# dashboard.net
KiCad netlist of a schematic drawn in EAGLE
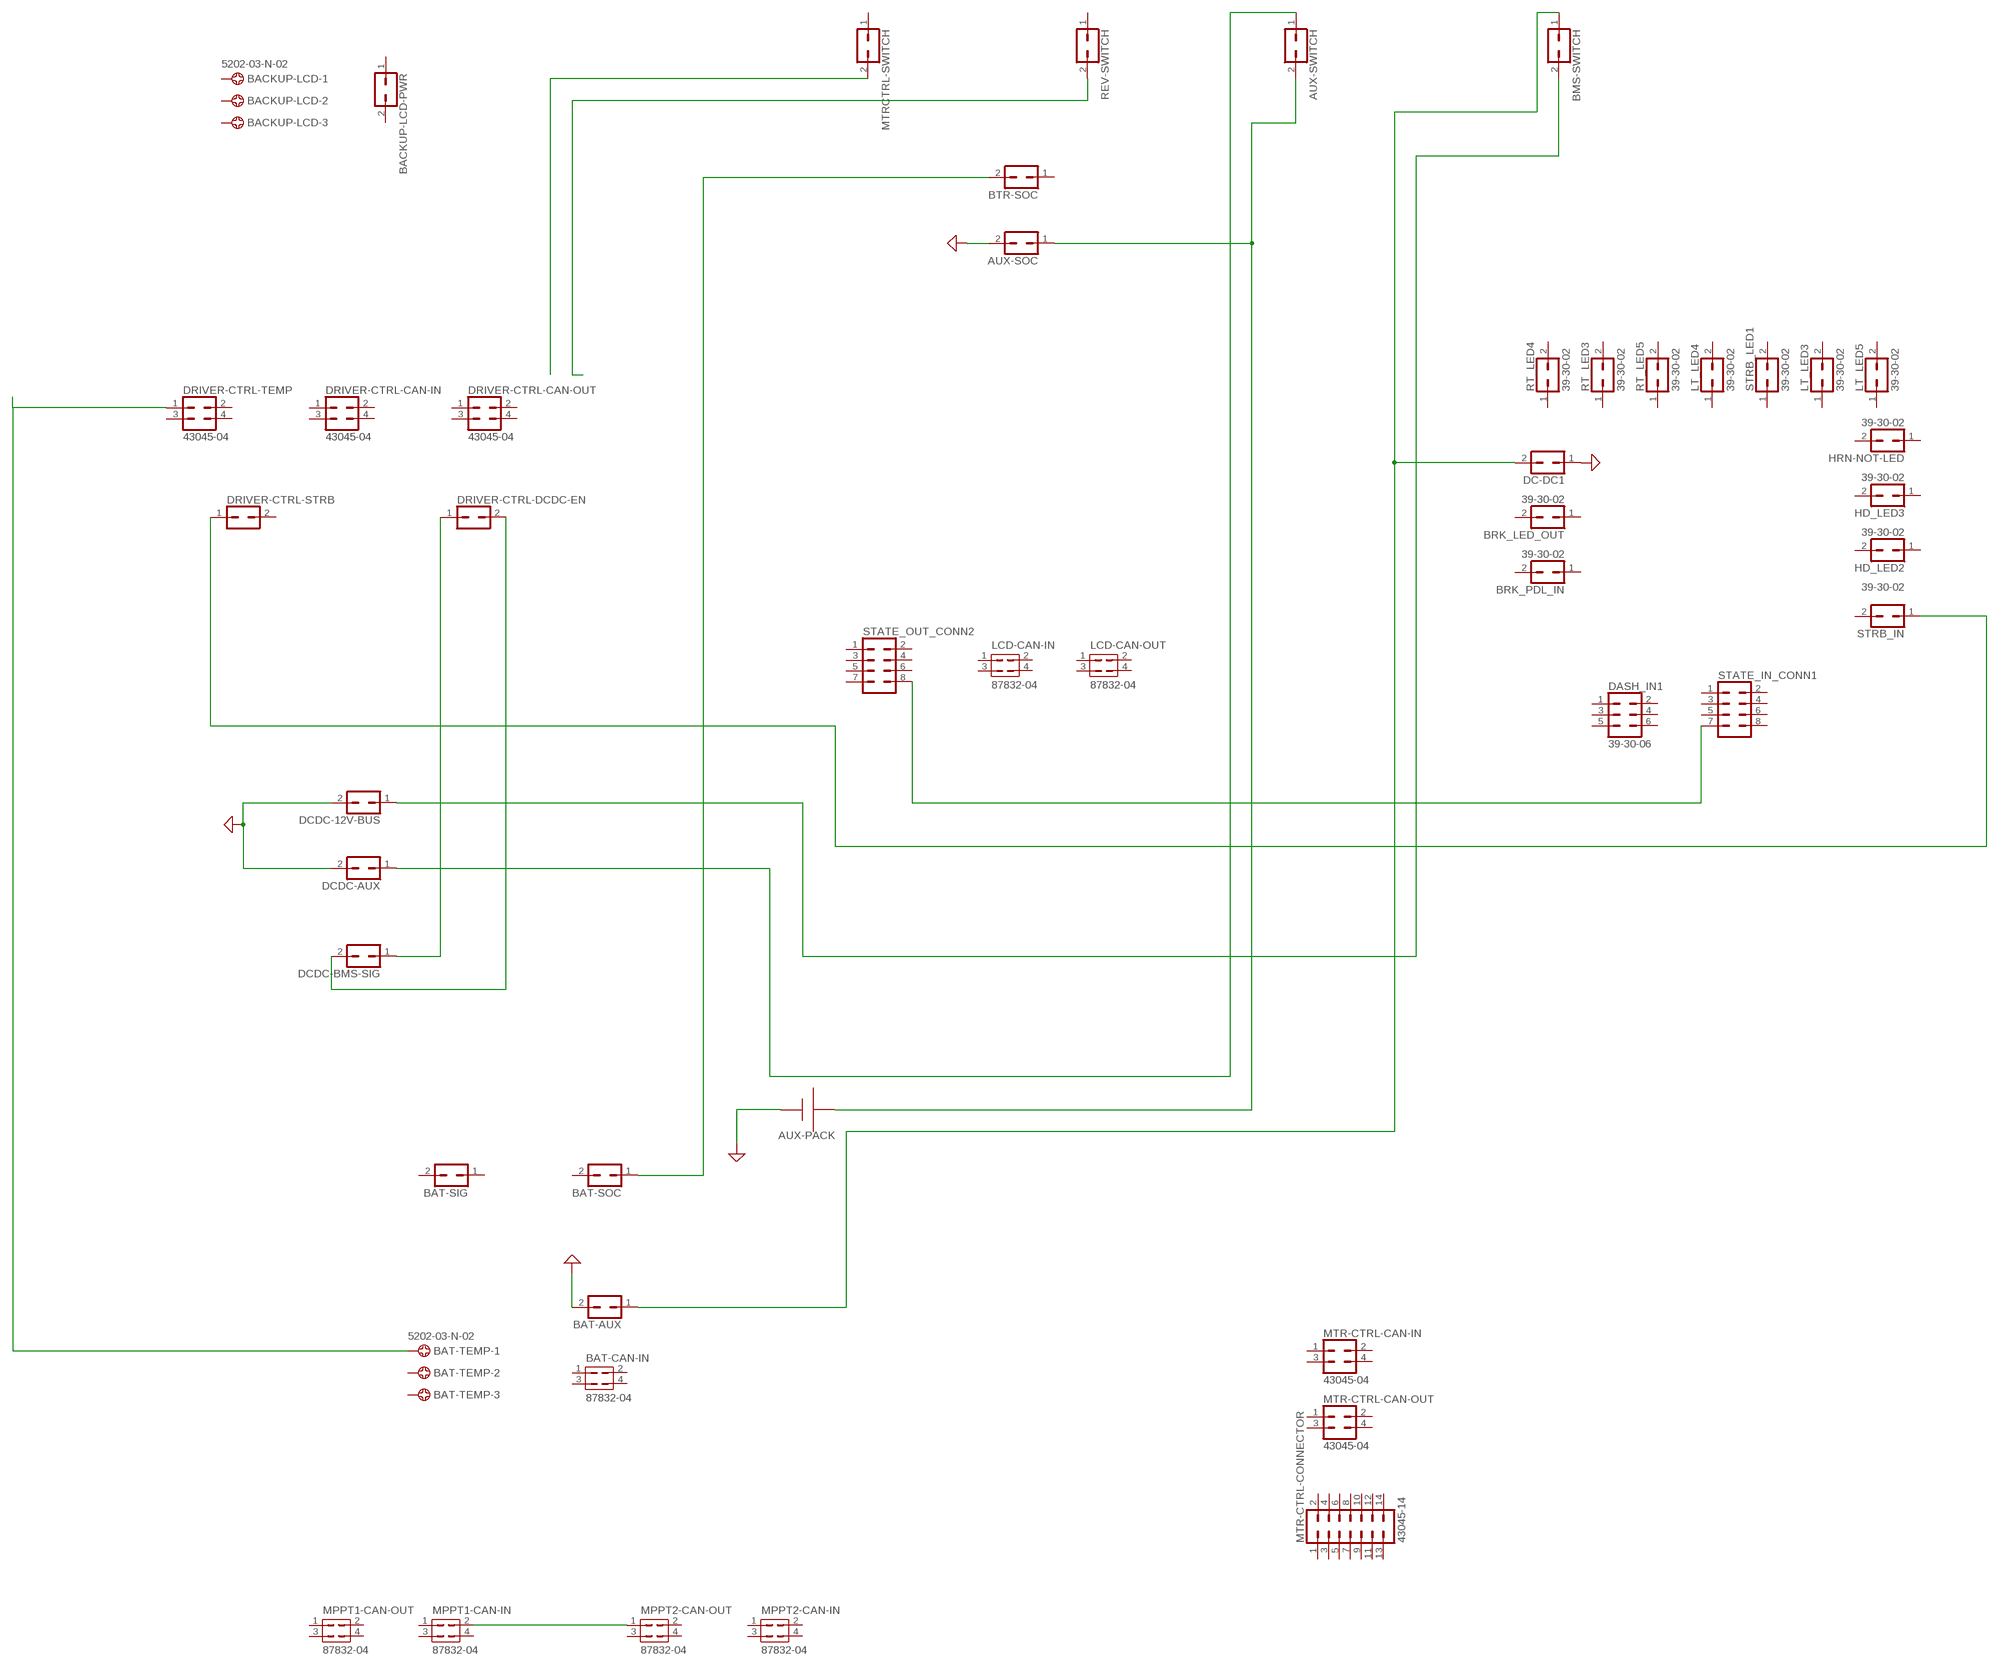
[diagram p0: schematic, sheet 1]

(export (version "E")
  (design (tool "Eeschema 10.0.6"))
  (components
    (comp (ref "AUX-PACK")
      (value "AAA")
      (footprint "eagle-import:12BH412")
      (libsource (lib "eagle-import") (part "AAA"))
    )
    (comp (ref "AUX-SOC")
      (value "39-30-02")
      (footprint "eagle-import:39-30-_02_")
      (libsource (lib "eagle-import") (part "39-30-?02?"))
    )
    (comp (ref "AUX-SWITCH")
      (value "39-30-02")
      (footprint "eagle-import:39-30-_02_")
      (libsource (lib "eagle-import") (part "39-30-?02?"))
    )
    (comp (ref "BACKUP-LCD")
      (value "5202-03-N-02")
      (footprint "eagle-import:5202-03-N-02")
      (libsource (lib "eagle-import") (part "5202-03-N-02"))
    )
    (comp (ref "BACKUP-LCD-PWR")
      (value "39-30-02")
      (footprint "eagle-import:39-30-_02_")
      (libsource (lib "eagle-import") (part "39-30-?02?"))
    )
    (comp (ref "BAT-AUX")
      (value "39-30-02")
      (footprint "eagle-import:39-30-_02_")
      (libsource (lib "eagle-import") (part "39-30-?02?"))
    )
    (comp (ref "BAT-CAN-IN")
      (value "87832-04")
      (footprint "eagle-import:87832-04")
      (fields (field (name "MF") "MOLEX"))
      (libsource (lib "eagle-import") (part "87832-04"))
    )
    (comp (ref "BAT-SIG")
      (value "39-30-02")
      (footprint "eagle-import:39-30-_02_")
      (libsource (lib "eagle-import") (part "39-30-?02?"))
    )
    (comp (ref "BAT-SOC")
      (value "39-30-02")
      (footprint "eagle-import:39-30-_02_")
      (libsource (lib "eagle-import") (part "39-30-?02?"))
    )
    (comp (ref "BAT-TEMP")
      (value "5202-03-N-02")
      (footprint "eagle-import:5202-03-N-02")
      (libsource (lib "eagle-import") (part "5202-03-N-02"))
    )
    (comp (ref "BMS-SWITCH")
      (value "39-30-02")
      (footprint "eagle-import:39-30-_02_")
      (libsource (lib "eagle-import") (part "39-30-?02?"))
    )
    (comp (ref "BRK_LED_OUT")
      (value "39-30-02")
      (footprint "eagle-import:39-30-_02_")
      (libsource (lib "eagle-import") (part "39-30-?02?"))
    )
    (comp (ref "BRK_PDL_IN")
      (value "39-30-02")
      (footprint "eagle-import:39-30-_02_")
      (libsource (lib "eagle-import") (part "39-30-?02?"))
    )
    (comp (ref "BTR-SOC")
      (value "39-30-02")
      (footprint "eagle-import:39-30-_02_")
      (libsource (lib "eagle-import") (part "39-30-?02?"))
    )
    (comp (ref "DASH_IN1")
      (value "39-30-06")
      (footprint "eagle-import:39-30-_06_")
      (libsource (lib "eagle-import") (part "39-30-?06?"))
    )
    (comp (ref "DC-DC1")
      (value "39-30-02")
      (footprint "eagle-import:39-30-_02_")
      (libsource (lib "eagle-import") (part "39-30-?02?"))
    )
    (comp (ref "DCDC-12V-BUS")
      (value "39-30-02")
      (footprint "eagle-import:39-30-_02_")
      (libsource (lib "eagle-import") (part "39-30-?02?"))
    )
    (comp (ref "DCDC-AUX")
      (value "39-30-02")
      (footprint "eagle-import:39-30-_02_")
      (libsource (lib "eagle-import") (part "39-30-?02?"))
    )
    (comp (ref "DCDC-BMS-SIG")
      (value "39-30-02")
      (footprint "eagle-import:39-30-_02_")
      (libsource (lib "eagle-import") (part "39-30-?02?"))
    )
    (comp (ref "DRIVER-CTRL-CAN-IN")
      (value "43045-04")
      (footprint "eagle-import:43045-04")
      (libsource (lib "eagle-import") (part "43045-04"))
    )
    (comp (ref "DRIVER-CTRL-CAN-OUT")
      (value "43045-04")
      (footprint "eagle-import:43045-04")
      (libsource (lib "eagle-import") (part "43045-04"))
    )
    (comp (ref "DRIVER-CTRL-DCDC-EN")
      (value "43045-02")
      (footprint "eagle-import:43045-02")
      (libsource (lib "eagle-import") (part "43045-02"))
    )
    (comp (ref "DRIVER-CTRL-STRB")
      (value "43045-02")
      (footprint "eagle-import:43045-02")
      (libsource (lib "eagle-import") (part "43045-02"))
    )
    (comp (ref "DRIVER-CTRL-TEMP")
      (value "43045-04")
      (footprint "eagle-import:43045-04")
      (libsource (lib "eagle-import") (part "43045-04"))
    )
    (comp (ref "HD_LED2")
      (value "39-30-02")
      (footprint "eagle-import:39-30-_02_")
      (libsource (lib "eagle-import") (part "39-30-?02?"))
    )
    (comp (ref "HD_LED3")
      (value "39-30-02")
      (footprint "eagle-import:39-30-_02_")
      (libsource (lib "eagle-import") (part "39-30-?02?"))
    )
    (comp (ref "HRN-NOT-LED")
      (value "39-30-02")
      (footprint "eagle-import:39-30-_02_")
      (libsource (lib "eagle-import") (part "39-30-?02?"))
    )
    (comp (ref "LCD-CAN-IN")
      (value "87832-04")
      (footprint "eagle-import:87832-04")
      (fields (field (name "MF") "MOLEX"))
      (libsource (lib "eagle-import") (part "87832-04"))
    )
    (comp (ref "LCD-CAN-OUT")
      (value "87832-04")
      (footprint "eagle-import:87832-04")
      (fields (field (name "MF") "MOLEX"))
      (libsource (lib "eagle-import") (part "87832-04"))
    )
    (comp (ref "LT_LED3")
      (value "39-30-02")
      (footprint "eagle-import:39-30-_02_")
      (libsource (lib "eagle-import") (part "39-30-?02?"))
    )
    (comp (ref "LT_LED4")
      (value "39-30-02")
      (footprint "eagle-import:39-30-_02_")
      (libsource (lib "eagle-import") (part "39-30-?02?"))
    )
    (comp (ref "LT_LED5")
      (value "39-30-02")
      (footprint "eagle-import:39-30-_02_")
      (libsource (lib "eagle-import") (part "39-30-?02?"))
    )
    (comp (ref "MPPT1-CAN-IN")
      (value "87832-04")
      (footprint "eagle-import:87832-04")
      (fields (field (name "MF") "MOLEX"))
      (libsource (lib "eagle-import") (part "87832-04"))
    )
    (comp (ref "MPPT1-CAN-OUT")
      (value "87832-04")
      (footprint "eagle-import:87832-04")
      (fields (field (name "MF") "MOLEX"))
      (libsource (lib "eagle-import") (part "87832-04"))
    )
    (comp (ref "MPPT2-CAN-IN")
      (value "87832-04")
      (footprint "eagle-import:87832-04")
      (fields (field (name "MF") "MOLEX"))
      (libsource (lib "eagle-import") (part "87832-04"))
    )
    (comp (ref "MPPT2-CAN-OUT")
      (value "87832-04")
      (footprint "eagle-import:87832-04")
      (fields (field (name "MF") "MOLEX"))
      (libsource (lib "eagle-import") (part "87832-04"))
    )
    (comp (ref "MTR-CTRL-CAN-IN")
      (value "43045-04")
      (footprint "eagle-import:43045-04")
      (libsource (lib "eagle-import") (part "43045-04"))
    )
    (comp (ref "MTR-CTRL-CAN-OUT")
      (value "43045-04")
      (footprint "eagle-import:43045-04")
      (libsource (lib "eagle-import") (part "43045-04"))
    )
    (comp (ref "MTR-CTRL-CONNECTOR")
      (value "43045-14")
      (footprint "eagle-import:43045-14")
      (libsource (lib "eagle-import") (part "43045-14"))
    )
    (comp (ref "MTRCTRL-SWITCH")
      (value "39-30-02")
      (footprint "eagle-import:39-30-_02_")
      (libsource (lib "eagle-import") (part "39-30-?02?"))
    )
    (comp (ref "REV-SWITCH")
      (value "39-30-02")
      (footprint "eagle-import:39-30-_02_")
      (libsource (lib "eagle-import") (part "39-30-?02?"))
    )
    (comp (ref "RT_LED3")
      (value "39-30-02")
      (footprint "eagle-import:39-30-_02_")
      (libsource (lib "eagle-import") (part "39-30-?02?"))
    )
    (comp (ref "RT_LED4")
      (value "39-30-02")
      (footprint "eagle-import:39-30-_02_")
      (libsource (lib "eagle-import") (part "39-30-?02?"))
    )
    (comp (ref "RT_LED5")
      (value "39-30-02")
      (footprint "eagle-import:39-30-_02_")
      (libsource (lib "eagle-import") (part "39-30-?02?"))
    )
    (comp (ref "STATE_IN_CONN1")
      (value "39-30-08")
      (footprint "eagle-import:39-30-_08_")
      (libsource (lib "eagle-import") (part "39-30-?08?"))
    )
    (comp (ref "STATE_OUT_CONN2")
      (value "39-30-08")
      (footprint "eagle-import:39-30-_08_")
      (libsource (lib "eagle-import") (part "39-30-?08?"))
    )
    (comp (ref "STRB_IN")
      (value "39-30-02")
      (footprint "eagle-import:39-30-_02_")
      (libsource (lib "eagle-import") (part "39-30-?02?"))
    )
    (comp (ref "STRB_LED1")
      (value "39-30-02")
      (footprint "eagle-import:39-30-_02_")
      (libsource (lib "eagle-import") (part "39-30-?02?"))
    )
  )
  (nets
    (net (code "1") (name "Net-(AUX-PACK-Pad-)") (class "Default")
      (node (ref "AUX-PACK") (pin "-") (pinfunction "-_-") (pintype "bidirectional"))
      (node (ref "AUX-SOC") (pin "1") (pinfunction "1_1") (pintype "passive"))
      (node (ref "AUX-SWITCH") (pin "2") (pinfunction "2_2") (pintype "passive"))
    )
    (net (code "2") (name "Net-(AUX-SWITCH-Pad1)") (class "Default")
      (node (ref "AUX-SWITCH") (pin "1") (pinfunction "1_1") (pintype "passive"))
      (node (ref "DCDC-AUX") (pin "1") (pinfunction "1_1") (pintype "passive"))
    )
    (net (code "3") (name "Net-(BAT-AUX-Pad1)") (class "Default")
      (node (ref "BAT-AUX") (pin "1") (pinfunction "1_1") (pintype "passive"))
      (node (ref "BMS-SWITCH") (pin "1") (pinfunction "1_1") (pintype "passive"))
      (node (ref "DC-DC1") (pin "2") (pinfunction "2_2") (pintype "passive"))
    )
    (net (code "4") (name "Net-(BAT-SOC-Pad1)") (class "Default")
      (node (ref "BAT-SOC") (pin "1") (pinfunction "1_1") (pintype "passive"))
      (node (ref "BTR-SOC") (pin "2") (pinfunction "2_2") (pintype "passive"))
    )
    (net (code "5") (name "Net-(BAT-TEMP-Pad1)") (class "Default")
      (node (ref "BAT-TEMP") (pin "1") (pinfunction "1_1") (pintype "passive"))
      (node (ref "DRIVER-CTRL-TEMP") (pin "1") (pinfunction "1_1") (pintype "passive"))
    )
    (net (code "6") (name "Net-(BMS-SWITCH-Pad2)") (class "Default")
      (node (ref "BMS-SWITCH") (pin "2") (pinfunction "2_2") (pintype "passive"))
      (node (ref "DCDC-12V-BUS") (pin "1") (pinfunction "1_1") (pintype "passive"))
    )
    (net (code "7") (name "Net-(DCDC-BMS-SIG-Pad1)") (class "Default")
      (node (ref "DCDC-BMS-SIG") (pin "1") (pinfunction "1_1") (pintype "passive"))
      (node (ref "DRIVER-CTRL-DCDC-EN") (pin "1") (pinfunction "1_1") (pintype "passive"))
    )
    (net (code "8") (name "Net-(DCDC-BMS-SIG-Pad2)") (class "Default")
      (node (ref "DCDC-BMS-SIG") (pin "2") (pinfunction "2_2") (pintype "passive"))
      (node (ref "DRIVER-CTRL-DCDC-EN") (pin "2") (pinfunction "2_2") (pintype "passive"))
    )
    (net (code "9") (name "Net-(DRIVER-CTRL-STRB-Pad1)") (class "Default")
      (node (ref "DRIVER-CTRL-STRB") (pin "1") (pinfunction "1_1") (pintype "passive"))
      (node (ref "STRB_IN") (pin "1") (pinfunction "1_1") (pintype "passive"))
    )
    (net (code "10") (name "Net-(MPPT1-CAN-IN-Pad2)") (class "Default")
      (node (ref "MPPT1-CAN-IN") (pin "2") (pinfunction "2_2") (pintype "passive"))
      (node (ref "MPPT2-CAN-OUT") (pin "1") (pinfunction "1_1") (pintype "passive"))
    )
    (net (code "11") (name "Net-(STATE_IN_CONN1-Pad7)") (class "Default")
      (node (ref "STATE_IN_CONN1") (pin "7") (pinfunction "7_7") (pintype "passive"))
      (node (ref "STATE_OUT_CONN2") (pin "8") (pinfunction "8_8") (pintype "passive"))
    )
    (net (code "12") (name "SUP") (class "Default")
      (node (ref "AUX-PACK") (pin "+") (pinfunction "+_+") (pintype "bidirectional"))
      (node (ref "AUX-SOC") (pin "2") (pinfunction "2_2") (pintype "passive"))
      (node (ref "BAT-AUX") (pin "2") (pinfunction "2_2") (pintype "passive"))
      (node (ref "DC-DC1") (pin "1") (pinfunction "1_1") (pintype "passive"))
      (node (ref "DCDC-12V-BUS") (pin "2") (pinfunction "2_2") (pintype "passive"))
      (node (ref "DCDC-AUX") (pin "2") (pinfunction "2_2") (pintype "passive"))
    )
    (net (code "13") (name "unconnected-(BACKUP-LCD-PWR-Pad1)") (class "Default")
      (node (ref "BACKUP-LCD-PWR") (pin "1") (pinfunction "1_1") (pintype "passive"))
    )
    (net (code "14") (name "unconnected-(BACKUP-LCD-PWR-Pad2)") (class "Default")
      (node (ref "BACKUP-LCD-PWR") (pin "2") (pinfunction "2_2") (pintype "passive"))
    )
    (net (code "15") (name "unconnected-(BACKUP-LCD-Pad1)") (class "Default")
      (node (ref "BACKUP-LCD") (pin "1") (pinfunction "1_1") (pintype "passive"))
    )
    (net (code "16") (name "unconnected-(BACKUP-LCDB-1-Pad2)") (class "Default")
      (node (ref "BACKUP-LCD") (pin "2") (pinfunction "1_2") (pintype "passive"))
    )
    (net (code "17") (name "unconnected-(BACKUP-LCDC-1-Pad3)") (class "Default")
      (node (ref "BACKUP-LCD") (pin "3") (pinfunction "1_3") (pintype "passive"))
    )
    (net (code "18") (name "unconnected-(BAT-CAN-IN-Pad1)") (class "Default")
      (node (ref "BAT-CAN-IN") (pin "1") (pinfunction "1_1") (pintype "passive"))
    )
    (net (code "19") (name "unconnected-(BAT-CAN-IN-Pad2)") (class "Default")
      (node (ref "BAT-CAN-IN") (pin "2") (pinfunction "2_2") (pintype "passive"))
    )
    (net (code "20") (name "unconnected-(BAT-CAN-IN-Pad3)") (class "Default")
      (node (ref "BAT-CAN-IN") (pin "3") (pinfunction "3_3") (pintype "passive"))
    )
    (net (code "21") (name "unconnected-(BAT-CAN-IN-Pad4)") (class "Default")
      (node (ref "BAT-CAN-IN") (pin "4") (pinfunction "4_4") (pintype "passive"))
    )
    (net (code "22") (name "unconnected-(BAT-SIG-Pad1)") (class "Default")
      (node (ref "BAT-SIG") (pin "1") (pinfunction "1_1") (pintype "passive"))
    )
    (net (code "23") (name "unconnected-(BAT-SIG-Pad2)") (class "Default")
      (node (ref "BAT-SIG") (pin "2") (pinfunction "2_2") (pintype "passive"))
    )
    (net (code "24") (name "unconnected-(BAT-SOC-Pad2)") (class "Default")
      (node (ref "BAT-SOC") (pin "2") (pinfunction "2_2") (pintype "passive"))
    )
    (net (code "25") (name "unconnected-(BAT-TEMPB-1-Pad2)") (class "Default")
      (node (ref "BAT-TEMP") (pin "2") (pinfunction "1_2") (pintype "passive"))
    )
    (net (code "26") (name "unconnected-(BAT-TEMPC-1-Pad3)") (class "Default")
      (node (ref "BAT-TEMP") (pin "3") (pinfunction "1_3") (pintype "passive"))
    )
    (net (code "27") (name "unconnected-(BRK_LED_OUT-Pad1)") (class "Default")
      (node (ref "BRK_LED_OUT") (pin "1") (pinfunction "1_1") (pintype "passive"))
    )
    (net (code "28") (name "unconnected-(BRK_LED_OUT-Pad2)") (class "Default")
      (node (ref "BRK_LED_OUT") (pin "2") (pinfunction "2_2") (pintype "passive"))
    )
    (net (code "29") (name "unconnected-(BRK_PDL_IN-Pad1)") (class "Default")
      (node (ref "BRK_PDL_IN") (pin "1") (pinfunction "1_1") (pintype "passive"))
    )
    (net (code "30") (name "unconnected-(BRK_PDL_IN-Pad2)") (class "Default")
      (node (ref "BRK_PDL_IN") (pin "2") (pinfunction "2_2") (pintype "passive"))
    )
    (net (code "31") (name "unconnected-(BTR-SOC-Pad1)") (class "Default")
      (node (ref "BTR-SOC") (pin "1") (pinfunction "1_1") (pintype "passive"))
    )
    (net (code "32") (name "unconnected-(DASH_IN1-Pad1)") (class "Default")
      (node (ref "DASH_IN1") (pin "1") (pinfunction "1_1") (pintype "passive"))
    )
    (net (code "33") (name "unconnected-(DASH_IN1-Pad2)") (class "Default")
      (node (ref "DASH_IN1") (pin "2") (pinfunction "2_2") (pintype "passive"))
    )
    (net (code "34") (name "unconnected-(DASH_IN1-Pad3)") (class "Default")
      (node (ref "DASH_IN1") (pin "3") (pinfunction "3_3") (pintype "passive"))
    )
    (net (code "35") (name "unconnected-(DASH_IN1-Pad4)") (class "Default")
      (node (ref "DASH_IN1") (pin "4") (pinfunction "4_4") (pintype "passive"))
    )
    (net (code "36") (name "unconnected-(DASH_IN1-Pad5)") (class "Default")
      (node (ref "DASH_IN1") (pin "5") (pinfunction "5_5") (pintype "passive"))
    )
    (net (code "37") (name "unconnected-(DASH_IN1-Pad6)") (class "Default")
      (node (ref "DASH_IN1") (pin "6") (pinfunction "6_6") (pintype "passive"))
    )
    (net (code "38") (name "unconnected-(DRIVER-CTRL-CAN-IN-Pad1)") (class "Default")
      (node (ref "DRIVER-CTRL-CAN-IN") (pin "1") (pinfunction "1_1") (pintype "passive"))
    )
    (net (code "39") (name "unconnected-(DRIVER-CTRL-CAN-IN-Pad2)") (class "Default")
      (node (ref "DRIVER-CTRL-CAN-IN") (pin "2") (pinfunction "2_2") (pintype "passive"))
    )
    (net (code "40") (name "unconnected-(DRIVER-CTRL-CAN-IN-Pad3)") (class "Default")
      (node (ref "DRIVER-CTRL-CAN-IN") (pin "3") (pinfunction "3_3") (pintype "passive"))
    )
    (net (code "41") (name "unconnected-(DRIVER-CTRL-CAN-IN-Pad4)") (class "Default")
      (node (ref "DRIVER-CTRL-CAN-IN") (pin "4") (pinfunction "4_4") (pintype "passive"))
    )
    (net (code "42") (name "unconnected-(DRIVER-CTRL-CAN-OUT-Pad1)") (class "Default")
      (node (ref "DRIVER-CTRL-CAN-OUT") (pin "1") (pinfunction "1_1") (pintype "passive"))
    )
    (net (code "43") (name "unconnected-(DRIVER-CTRL-CAN-OUT-Pad2)") (class "Default")
      (node (ref "DRIVER-CTRL-CAN-OUT") (pin "2") (pinfunction "2_2") (pintype "passive"))
    )
    (net (code "44") (name "unconnected-(DRIVER-CTRL-CAN-OUT-Pad3)") (class "Default")
      (node (ref "DRIVER-CTRL-CAN-OUT") (pin "3") (pinfunction "3_3") (pintype "passive"))
    )
    (net (code "45") (name "unconnected-(DRIVER-CTRL-CAN-OUT-Pad4)") (class "Default")
      (node (ref "DRIVER-CTRL-CAN-OUT") (pin "4") (pinfunction "4_4") (pintype "passive"))
    )
    (net (code "46") (name "unconnected-(DRIVER-CTRL-STRB-Pad2)") (class "Default")
      (node (ref "DRIVER-CTRL-STRB") (pin "2") (pinfunction "2_2") (pintype "passive"))
    )
    (net (code "47") (name "unconnected-(DRIVER-CTRL-TEMP-Pad2)") (class "Default")
      (node (ref "DRIVER-CTRL-TEMP") (pin "2") (pinfunction "2_2") (pintype "passive"))
    )
    (net (code "48") (name "unconnected-(DRIVER-CTRL-TEMP-Pad3)") (class "Default")
      (node (ref "DRIVER-CTRL-TEMP") (pin "3") (pinfunction "3_3") (pintype "passive"))
    )
    (net (code "49") (name "unconnected-(DRIVER-CTRL-TEMP-Pad4)") (class "Default")
      (node (ref "DRIVER-CTRL-TEMP") (pin "4") (pinfunction "4_4") (pintype "passive"))
    )
    (net (code "50") (name "unconnected-(HD_LED2-Pad1)") (class "Default")
      (node (ref "HD_LED2") (pin "1") (pinfunction "1_1") (pintype "passive"))
    )
    (net (code "51") (name "unconnected-(HD_LED2-Pad2)") (class "Default")
      (node (ref "HD_LED2") (pin "2") (pinfunction "2_2") (pintype "passive"))
    )
    (net (code "52") (name "unconnected-(HD_LED3-Pad1)") (class "Default")
      (node (ref "HD_LED3") (pin "1") (pinfunction "1_1") (pintype "passive"))
    )
    (net (code "53") (name "unconnected-(HD_LED3-Pad2)") (class "Default")
      (node (ref "HD_LED3") (pin "2") (pinfunction "2_2") (pintype "passive"))
    )
    (net (code "54") (name "unconnected-(HRN-NOT-LED-Pad1)") (class "Default")
      (node (ref "HRN-NOT-LED") (pin "1") (pinfunction "1_1") (pintype "passive"))
    )
    (net (code "55") (name "unconnected-(HRN-NOT-LED-Pad2)") (class "Default")
      (node (ref "HRN-NOT-LED") (pin "2") (pinfunction "2_2") (pintype "passive"))
    )
    (net (code "56") (name "unconnected-(LCD-CAN-IN-Pad1)") (class "Default")
      (node (ref "LCD-CAN-IN") (pin "1") (pinfunction "1_1") (pintype "passive"))
    )
    (net (code "57") (name "unconnected-(LCD-CAN-IN-Pad2)") (class "Default")
      (node (ref "LCD-CAN-IN") (pin "2") (pinfunction "2_2") (pintype "passive"))
    )
    (net (code "58") (name "unconnected-(LCD-CAN-IN-Pad3)") (class "Default")
      (node (ref "LCD-CAN-IN") (pin "3") (pinfunction "3_3") (pintype "passive"))
    )
    (net (code "59") (name "unconnected-(LCD-CAN-IN-Pad4)") (class "Default")
      (node (ref "LCD-CAN-IN") (pin "4") (pinfunction "4_4") (pintype "passive"))
    )
    (net (code "60") (name "unconnected-(LCD-CAN-OUT-Pad1)") (class "Default")
      (node (ref "LCD-CAN-OUT") (pin "1") (pinfunction "1_1") (pintype "passive"))
    )
    (net (code "61") (name "unconnected-(LCD-CAN-OUT-Pad2)") (class "Default")
      (node (ref "LCD-CAN-OUT") (pin "2") (pinfunction "2_2") (pintype "passive"))
    )
    (net (code "62") (name "unconnected-(LCD-CAN-OUT-Pad3)") (class "Default")
      (node (ref "LCD-CAN-OUT") (pin "3") (pinfunction "3_3") (pintype "passive"))
    )
    (net (code "63") (name "unconnected-(LCD-CAN-OUT-Pad4)") (class "Default")
      (node (ref "LCD-CAN-OUT") (pin "4") (pinfunction "4_4") (pintype "passive"))
    )
    (net (code "64") (name "unconnected-(LT_LED3-Pad1)") (class "Default")
      (node (ref "LT_LED3") (pin "1") (pinfunction "1_1") (pintype "passive"))
    )
    (net (code "65") (name "unconnected-(LT_LED3-Pad2)") (class "Default")
      (node (ref "LT_LED3") (pin "2") (pinfunction "2_2") (pintype "passive"))
    )
    (net (code "66") (name "unconnected-(LT_LED4-Pad1)") (class "Default")
      (node (ref "LT_LED4") (pin "1") (pinfunction "1_1") (pintype "passive"))
    )
    (net (code "67") (name "unconnected-(LT_LED4-Pad2)") (class "Default")
      (node (ref "LT_LED4") (pin "2") (pinfunction "2_2") (pintype "passive"))
    )
    (net (code "68") (name "unconnected-(LT_LED5-Pad1)") (class "Default")
      (node (ref "LT_LED5") (pin "1") (pinfunction "1_1") (pintype "passive"))
    )
    (net (code "69") (name "unconnected-(LT_LED5-Pad2)") (class "Default")
      (node (ref "LT_LED5") (pin "2") (pinfunction "2_2") (pintype "passive"))
    )
    (net (code "70") (name "unconnected-(MPPT1-CAN-IN-Pad1)") (class "Default")
      (node (ref "MPPT1-CAN-IN") (pin "1") (pinfunction "1_1") (pintype "passive"))
    )
    (net (code "71") (name "unconnected-(MPPT1-CAN-IN-Pad3)") (class "Default")
      (node (ref "MPPT1-CAN-IN") (pin "3") (pinfunction "3_3") (pintype "passive"))
    )
    (net (code "72") (name "unconnected-(MPPT1-CAN-IN-Pad4)") (class "Default")
      (node (ref "MPPT1-CAN-IN") (pin "4") (pinfunction "4_4") (pintype "passive"))
    )
    (net (code "73") (name "unconnected-(MPPT1-CAN-OUT-Pad1)") (class "Default")
      (node (ref "MPPT1-CAN-OUT") (pin "1") (pinfunction "1_1") (pintype "passive"))
    )
    (net (code "74") (name "unconnected-(MPPT1-CAN-OUT-Pad2)") (class "Default")
      (node (ref "MPPT1-CAN-OUT") (pin "2") (pinfunction "2_2") (pintype "passive"))
    )
    (net (code "75") (name "unconnected-(MPPT1-CAN-OUT-Pad3)") (class "Default")
      (node (ref "MPPT1-CAN-OUT") (pin "3") (pinfunction "3_3") (pintype "passive"))
    )
    (net (code "76") (name "unconnected-(MPPT1-CAN-OUT-Pad4)") (class "Default")
      (node (ref "MPPT1-CAN-OUT") (pin "4") (pinfunction "4_4") (pintype "passive"))
    )
    (net (code "77") (name "unconnected-(MPPT2-CAN-IN-Pad1)") (class "Default")
      (node (ref "MPPT2-CAN-IN") (pin "1") (pinfunction "1_1") (pintype "passive"))
    )
    (net (code "78") (name "unconnected-(MPPT2-CAN-IN-Pad2)") (class "Default")
      (node (ref "MPPT2-CAN-IN") (pin "2") (pinfunction "2_2") (pintype "passive"))
    )
    (net (code "79") (name "unconnected-(MPPT2-CAN-IN-Pad3)") (class "Default")
      (node (ref "MPPT2-CAN-IN") (pin "3") (pinfunction "3_3") (pintype "passive"))
    )
    (net (code "80") (name "unconnected-(MPPT2-CAN-IN-Pad4)") (class "Default")
      (node (ref "MPPT2-CAN-IN") (pin "4") (pinfunction "4_4") (pintype "passive"))
    )
    (net (code "81") (name "unconnected-(MPPT2-CAN-OUT-Pad2)") (class "Default")
      (node (ref "MPPT2-CAN-OUT") (pin "2") (pinfunction "2_2") (pintype "passive"))
    )
    (net (code "82") (name "unconnected-(MPPT2-CAN-OUT-Pad3)") (class "Default")
      (node (ref "MPPT2-CAN-OUT") (pin "3") (pinfunction "3_3") (pintype "passive"))
    )
    (net (code "83") (name "unconnected-(MPPT2-CAN-OUT-Pad4)") (class "Default")
      (node (ref "MPPT2-CAN-OUT") (pin "4") (pinfunction "4_4") (pintype "passive"))
    )
    (net (code "84") (name "unconnected-(MTR-CTRL-CAN-IN-Pad1)") (class "Default")
      (node (ref "MTR-CTRL-CAN-IN") (pin "1") (pinfunction "1_1") (pintype "passive"))
    )
    (net (code "85") (name "unconnected-(MTR-CTRL-CAN-IN-Pad2)") (class "Default")
      (node (ref "MTR-CTRL-CAN-IN") (pin "2") (pinfunction "2_2") (pintype "passive"))
    )
    (net (code "86") (name "unconnected-(MTR-CTRL-CAN-IN-Pad3)") (class "Default")
      (node (ref "MTR-CTRL-CAN-IN") (pin "3") (pinfunction "3_3") (pintype "passive"))
    )
    (net (code "87") (name "unconnected-(MTR-CTRL-CAN-IN-Pad4)") (class "Default")
      (node (ref "MTR-CTRL-CAN-IN") (pin "4") (pinfunction "4_4") (pintype "passive"))
    )
    (net (code "88") (name "unconnected-(MTR-CTRL-CAN-OUT-Pad1)") (class "Default")
      (node (ref "MTR-CTRL-CAN-OUT") (pin "1") (pinfunction "1_1") (pintype "passive"))
    )
    (net (code "89") (name "unconnected-(MTR-CTRL-CAN-OUT-Pad2)") (class "Default")
      (node (ref "MTR-CTRL-CAN-OUT") (pin "2") (pinfunction "2_2") (pintype "passive"))
    )
    (net (code "90") (name "unconnected-(MTR-CTRL-CAN-OUT-Pad3)") (class "Default")
      (node (ref "MTR-CTRL-CAN-OUT") (pin "3") (pinfunction "3_3") (pintype "passive"))
    )
    (net (code "91") (name "unconnected-(MTR-CTRL-CAN-OUT-Pad4)") (class "Default")
      (node (ref "MTR-CTRL-CAN-OUT") (pin "4") (pinfunction "4_4") (pintype "passive"))
    )
    (net (code "92") (name "unconnected-(MTR-CTRL-CONNECTOR-Pad1)") (class "Default")
      (node (ref "MTR-CTRL-CONNECTOR") (pin "1") (pinfunction "1_1") (pintype "passive"))
    )
    (net (code "93") (name "unconnected-(MTR-CTRL-CONNECTOR-Pad2)") (class "Default")
      (node (ref "MTR-CTRL-CONNECTOR") (pin "2") (pinfunction "2_2") (pintype "passive"))
    )
    (net (code "94") (name "unconnected-(MTR-CTRL-CONNECTOR-Pad3)") (class "Default")
      (node (ref "MTR-CTRL-CONNECTOR") (pin "3") (pinfunction "3_3") (pintype "passive"))
    )
    (net (code "95") (name "unconnected-(MTR-CTRL-CONNECTOR-Pad4)") (class "Default")
      (node (ref "MTR-CTRL-CONNECTOR") (pin "4") (pinfunction "4_4") (pintype "passive"))
    )
    (net (code "96") (name "unconnected-(MTR-CTRL-CONNECTOR-Pad5)") (class "Default")
      (node (ref "MTR-CTRL-CONNECTOR") (pin "5") (pinfunction "5_5") (pintype "passive"))
    )
    (net (code "97") (name "unconnected-(MTR-CTRL-CONNECTOR-Pad6)") (class "Default")
      (node (ref "MTR-CTRL-CONNECTOR") (pin "6") (pinfunction "6_6") (pintype "passive"))
    )
    (net (code "98") (name "unconnected-(MTR-CTRL-CONNECTOR-Pad7)") (class "Default")
      (node (ref "MTR-CTRL-CONNECTOR") (pin "7") (pinfunction "7_7") (pintype "passive"))
    )
    (net (code "99") (name "unconnected-(MTR-CTRL-CONNECTOR-Pad8)") (class "Default")
      (node (ref "MTR-CTRL-CONNECTOR") (pin "8") (pinfunction "8_8") (pintype "passive"))
    )
    (net (code "100") (name "unconnected-(MTR-CTRL-CONNECTOR-Pad9)") (class "Default")
      (node (ref "MTR-CTRL-CONNECTOR") (pin "9") (pinfunction "9_9") (pintype "passive"))
    )
    (net (code "101") (name "unconnected-(MTR-CTRL-CONNECTOR-Pad10)") (class "Default")
      (node (ref "MTR-CTRL-CONNECTOR") (pin "10") (pinfunction "10_10") (pintype "passive"))
    )
    (net (code "102") (name "unconnected-(MTR-CTRL-CONNECTOR-Pad11)") (class "Default")
      (node (ref "MTR-CTRL-CONNECTOR") (pin "11") (pinfunction "11_11") (pintype "passive"))
    )
    (net (code "103") (name "unconnected-(MTR-CTRL-CONNECTOR-Pad12)") (class "Default")
      (node (ref "MTR-CTRL-CONNECTOR") (pin "12") (pinfunction "12_12") (pintype "passive"))
    )
    (net (code "104") (name "unconnected-(MTR-CTRL-CONNECTOR-Pad13)") (class "Default")
      (node (ref "MTR-CTRL-CONNECTOR") (pin "13") (pinfunction "13_13") (pintype "passive"))
    )
    (net (code "105") (name "unconnected-(MTR-CTRL-CONNECTOR-Pad14)") (class "Default")
      (node (ref "MTR-CTRL-CONNECTOR") (pin "14") (pinfunction "14_14") (pintype "passive"))
    )
    (net (code "106") (name "unconnected-(MTRCTRL-SWITCH-Pad1)") (class "Default")
      (node (ref "MTRCTRL-SWITCH") (pin "1") (pinfunction "1_1") (pintype "passive"))
    )
    (net (code "107") (name "unconnected-(MTRCTRL-SWITCH-Pad2)") (class "Default")
      (node (ref "MTRCTRL-SWITCH") (pin "2") (pinfunction "2_2") (pintype "passive"))
    )
    (net (code "108") (name "unconnected-(REV-SWITCH-Pad1)") (class "Default")
      (node (ref "REV-SWITCH") (pin "1") (pinfunction "1_1") (pintype "passive"))
    )
    (net (code "109") (name "unconnected-(REV-SWITCH-Pad2)") (class "Default")
      (node (ref "REV-SWITCH") (pin "2") (pinfunction "2_2") (pintype "passive"))
    )
    (net (code "110") (name "unconnected-(RT_LED3-Pad1)") (class "Default")
      (node (ref "RT_LED3") (pin "1") (pinfunction "1_1") (pintype "passive"))
    )
    (net (code "111") (name "unconnected-(RT_LED3-Pad2)") (class "Default")
      (node (ref "RT_LED3") (pin "2") (pinfunction "2_2") (pintype "passive"))
    )
    (net (code "112") (name "unconnected-(RT_LED4-Pad1)") (class "Default")
      (node (ref "RT_LED4") (pin "1") (pinfunction "1_1") (pintype "passive"))
    )
    (net (code "113") (name "unconnected-(RT_LED4-Pad2)") (class "Default")
      (node (ref "RT_LED4") (pin "2") (pinfunction "2_2") (pintype "passive"))
    )
    (net (code "114") (name "unconnected-(RT_LED5-Pad1)") (class "Default")
      (node (ref "RT_LED5") (pin "1") (pinfunction "1_1") (pintype "passive"))
    )
    (net (code "115") (name "unconnected-(RT_LED5-Pad2)") (class "Default")
      (node (ref "RT_LED5") (pin "2") (pinfunction "2_2") (pintype "passive"))
    )
    (net (code "116") (name "unconnected-(STATE_IN_CONN1-Pad1)") (class "Default")
      (node (ref "STATE_IN_CONN1") (pin "1") (pinfunction "1_1") (pintype "passive"))
    )
    (net (code "117") (name "unconnected-(STATE_IN_CONN1-Pad2)") (class "Default")
      (node (ref "STATE_IN_CONN1") (pin "2") (pinfunction "2_2") (pintype "passive"))
    )
    (net (code "118") (name "unconnected-(STATE_IN_CONN1-Pad3)") (class "Default")
      (node (ref "STATE_IN_CONN1") (pin "3") (pinfunction "3_3") (pintype "passive"))
    )
    (net (code "119") (name "unconnected-(STATE_IN_CONN1-Pad4)") (class "Default")
      (node (ref "STATE_IN_CONN1") (pin "4") (pinfunction "4_4") (pintype "passive"))
    )
    (net (code "120") (name "unconnected-(STATE_IN_CONN1-Pad5)") (class "Default")
      (node (ref "STATE_IN_CONN1") (pin "5") (pinfunction "5_5") (pintype "passive"))
    )
    (net (code "121") (name "unconnected-(STATE_IN_CONN1-Pad6)") (class "Default")
      (node (ref "STATE_IN_CONN1") (pin "6") (pinfunction "6_6") (pintype "passive"))
    )
    (net (code "122") (name "unconnected-(STATE_IN_CONN1-Pad8)") (class "Default")
      (node (ref "STATE_IN_CONN1") (pin "8") (pinfunction "8_8") (pintype "passive"))
    )
    (net (code "123") (name "unconnected-(STATE_OUT_CONN2-Pad1)") (class "Default")
      (node (ref "STATE_OUT_CONN2") (pin "1") (pinfunction "1_1") (pintype "passive"))
    )
    (net (code "124") (name "unconnected-(STATE_OUT_CONN2-Pad2)") (class "Default")
      (node (ref "STATE_OUT_CONN2") (pin "2") (pinfunction "2_2") (pintype "passive"))
    )
    (net (code "125") (name "unconnected-(STATE_OUT_CONN2-Pad3)") (class "Default")
      (node (ref "STATE_OUT_CONN2") (pin "3") (pinfunction "3_3") (pintype "passive"))
    )
    (net (code "126") (name "unconnected-(STATE_OUT_CONN2-Pad4)") (class "Default")
      (node (ref "STATE_OUT_CONN2") (pin "4") (pinfunction "4_4") (pintype "passive"))
    )
    (net (code "127") (name "unconnected-(STATE_OUT_CONN2-Pad5)") (class "Default")
      (node (ref "STATE_OUT_CONN2") (pin "5") (pinfunction "5_5") (pintype "passive"))
    )
    (net (code "128") (name "unconnected-(STATE_OUT_CONN2-Pad6)") (class "Default")
      (node (ref "STATE_OUT_CONN2") (pin "6") (pinfunction "6_6") (pintype "passive"))
    )
    (net (code "129") (name "unconnected-(STATE_OUT_CONN2-Pad7)") (class "Default")
      (node (ref "STATE_OUT_CONN2") (pin "7") (pinfunction "7_7") (pintype "passive"))
    )
    (net (code "130") (name "unconnected-(STRB_IN-Pad2)") (class "Default")
      (node (ref "STRB_IN") (pin "2") (pinfunction "2_2") (pintype "passive"))
    )
    (net (code "131") (name "unconnected-(STRB_LED1-Pad1)") (class "Default")
      (node (ref "STRB_LED1") (pin "1") (pinfunction "1_1") (pintype "passive"))
    )
    (net (code "132") (name "unconnected-(STRB_LED1-Pad2)") (class "Default")
      (node (ref "STRB_LED1") (pin "2") (pinfunction "2_2") (pintype "passive"))
    )
  )
)
